# Wheel.net
KiCad netlist of a schematic drawn in EAGLE
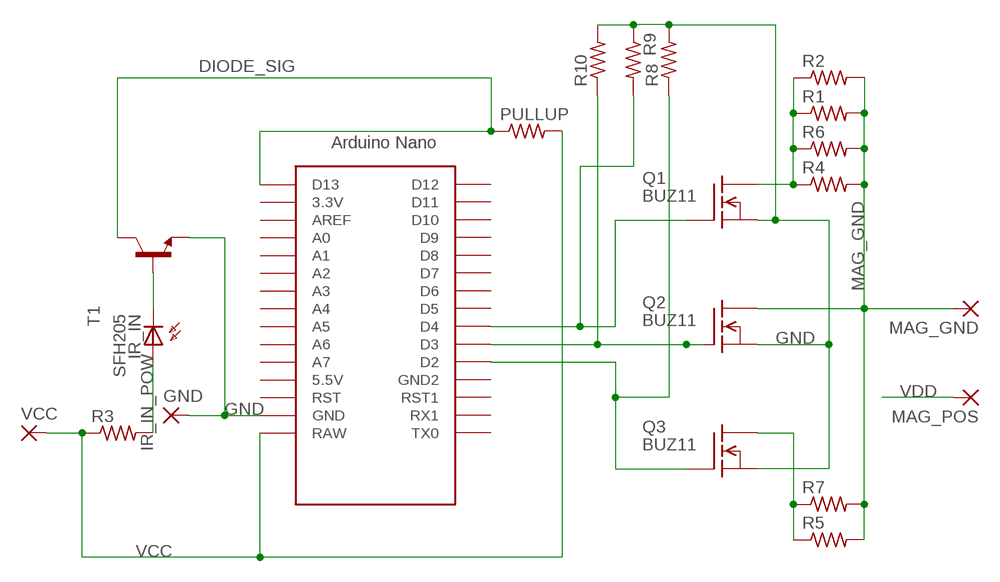
[diagram p0: schematic, sheet 1]

(export (version "E")
  (design (tool "Eeschema 10.0.6"))
  (components
    (comp (ref "GND")
      (value "3,81/1,4")
      (footprint "eagle-import:3,81_1,4")
      (libsource (lib "eagle-import") (part "3,81/1,4"))
    )
    (comp (ref "IR_IN")
      (value "SFH205")
      (footprint "eagle-import:SFH205")
      (libsource (lib "eagle-import") (part "SFH205"))
    )
    (comp (ref "MAG_GND")
      (value "3,81/1,4")
      (footprint "eagle-import:3,81_1,4")
      (libsource (lib "eagle-import") (part "3,81/1,4"))
    )
    (comp (ref "MAG_POS")
      (value "3,81/1,4")
      (footprint "eagle-import:3,81_1,4")
      (libsource (lib "eagle-import") (part "3,81/1,4"))
    )
    (comp (ref "PULLUP")
      (value "R-US_0204/7")
      (footprint "eagle-import:0204_7")
      (libsource (lib "eagle-import") (part "R-US_0204/7"))
    )
    (comp (ref "Q1")
      (value "BUZ11")
      (footprint "eagle-import:TO220")
      (libsource (lib "eagle-import") (part "BUZ11"))
    )
    (comp (ref "Q2")
      (value "BUZ11")
      (footprint "eagle-import:TO220")
      (libsource (lib "eagle-import") (part "BUZ11"))
    )
    (comp (ref "Q3")
      (value "BUZ11")
      (footprint "eagle-import:TO220")
      (libsource (lib "eagle-import") (part "BUZ11"))
    )
    (comp (ref "R1")
      (value "R-US_0204/7")
      (footprint "eagle-import:0204_7")
      (libsource (lib "eagle-import") (part "R-US_0204/7"))
    )
    (comp (ref "R2")
      (value "R-US_0204/7")
      (footprint "eagle-import:0204_7")
      (libsource (lib "eagle-import") (part "R-US_0204/7"))
    )
    (comp (ref "R3")
      (value "R-US_0204/7")
      (footprint "eagle-import:0204_7")
      (libsource (lib "eagle-import") (part "R-US_0204/7"))
    )
    (comp (ref "R4")
      (value "R-US_0204/7")
      (footprint "eagle-import:0204_7")
      (libsource (lib "eagle-import") (part "R-US_0204/7"))
    )
    (comp (ref "R5")
      (value "R-US_0204/7")
      (footprint "eagle-import:0204_7")
      (libsource (lib "eagle-import") (part "R-US_0204/7"))
    )
    (comp (ref "R6")
      (value "R-US_0204/7")
      (footprint "eagle-import:0204_7")
      (libsource (lib "eagle-import") (part "R-US_0204/7"))
    )
    (comp (ref "R7")
      (value "R-US_0204/7")
      (footprint "eagle-import:0204_7")
      (libsource (lib "eagle-import") (part "R-US_0204/7"))
    )
    (comp (ref "R8")
      (value "R-US_0204/7")
      (footprint "eagle-import:0204_7")
      (libsource (lib "eagle-import") (part "R-US_0204/7"))
    )
    (comp (ref "R9")
      (value "R-US_0204/7")
      (footprint "eagle-import:0204_7")
      (libsource (lib "eagle-import") (part "R-US_0204/7"))
    )
    (comp (ref "R10")
      (value "R-US_0204/7")
      (footprint "eagle-import:0204_7")
      (libsource (lib "eagle-import") (part "R-US_0204/7"))
    )
    (comp (ref "T1")
      (value "-NPN-TO92-EBC")
      (footprint "eagle-import:TO92-EBC")
      (libsource (lib "eagle-import") (part "-NPN-TO92-EBC"))
    )
    (comp (ref "U$1")
      (value "NANO")
      (footprint "eagle-import:NANO")
      (libsource (lib "eagle-import") (part "NANO"))
    )
    (comp (ref "VCC")
      (value "3,81/1,4")
      (footprint "eagle-import:3,81_1,4")
      (libsource (lib "eagle-import") (part "3,81/1,4"))
    )
  )
  (nets
    (net (code "1") (name "/DIODE_SIG") (class "Default")
      (node (ref "PULLUP") (pin "1") (pinfunction "1_1") (pintype "passive"))
      (node (ref "T1") (pin "C") (pinfunction "C_C") (pintype "passive"))
      (node (ref "U$1") (pin "D13") (pinfunction "D13_D13") (pintype "bidirectional"))
    )
    (net (code "2") (name "/GND") (class "Default")
      (node (ref "GND") (pin "1") (pinfunction "P_1") (pintype "passive"))
      (node (ref "Q1") (pin "3") (pinfunction "S_3") (pintype "passive"))
      (node (ref "Q2") (pin "3") (pinfunction "S_3") (pintype "passive"))
      (node (ref "Q3") (pin "3") (pinfunction "S_3") (pintype "passive"))
      (node (ref "R10") (pin "2") (pinfunction "2_2") (pintype "passive"))
      (node (ref "R8") (pin "2") (pinfunction "2_2") (pintype "passive"))
      (node (ref "R9") (pin "1") (pinfunction "1_1") (pintype "passive"))
      (node (ref "T1") (pin "E") (pinfunction "E_E") (pintype "passive"))
      (node (ref "U$1") (pin "GND") (pinfunction "GND_GND") (pintype "bidirectional"))
    )
    (net (code "3") (name "/IR_IN_POW") (class "Default")
      (node (ref "IR_IN") (pin "A") (pinfunction "A_A") (pintype "passive"))
      (node (ref "R3") (pin "2") (pinfunction "2_2") (pintype "passive"))
    )
    (net (code "4") (name "/MAG_GND") (class "Default")
      (node (ref "MAG_GND") (pin "1") (pinfunction "P_1") (pintype "passive"))
      (node (ref "Q2") (pin "2") (pinfunction "D_2") (pintype "passive"))
      (node (ref "R1") (pin "2") (pinfunction "2_2") (pintype "passive"))
      (node (ref "R2") (pin "2") (pinfunction "2_2") (pintype "passive"))
      (node (ref "R4") (pin "2") (pinfunction "2_2") (pintype "passive"))
      (node (ref "R5") (pin "2") (pinfunction "2_2") (pintype "passive"))
      (node (ref "R6") (pin "2") (pinfunction "2_2") (pintype "passive"))
      (node (ref "R7") (pin "2") (pinfunction "2_2") (pintype "passive"))
    )
    (net (code "5") (name "/VCC") (class "Default")
      (node (ref "PULLUP") (pin "2") (pinfunction "2_2") (pintype "passive"))
      (node (ref "R3") (pin "1") (pinfunction "1_1") (pintype "passive"))
      (node (ref "U$1") (pin "RAW") (pinfunction "RAW_RAW") (pintype "bidirectional"))
      (node (ref "VCC") (pin "1") (pinfunction "P_1") (pintype "passive"))
    )
    (net (code "6") (name "/VDD") (class "Default")
      (node (ref "MAG_POS") (pin "1") (pinfunction "P_1") (pintype "passive"))
    )
    (net (code "7") (name "Net-(IR_IN-C)") (class "Default")
      (node (ref "IR_IN") (pin "K") (pinfunction "C_K") (pintype "passive"))
      (node (ref "T1") (pin "B") (pinfunction "B_B") (pintype "passive"))
    )
    (net (code "8") (name "Net-(Q1-D)") (class "Default")
      (node (ref "Q1") (pin "2") (pinfunction "D_2") (pintype "passive"))
      (node (ref "R1") (pin "1") (pinfunction "1_1") (pintype "passive"))
      (node (ref "R2") (pin "1") (pinfunction "1_1") (pintype "passive"))
      (node (ref "R4") (pin "1") (pinfunction "1_1") (pintype "passive"))
      (node (ref "R6") (pin "1") (pinfunction "1_1") (pintype "passive"))
    )
    (net (code "9") (name "Net-(Q1-G)") (class "Default")
      (node (ref "Q1") (pin "1") (pinfunction "G_1") (pintype "passive"))
      (node (ref "R9") (pin "2") (pinfunction "2_2") (pintype "passive"))
      (node (ref "U$1") (pin "D4") (pinfunction "D4_D4") (pintype "bidirectional"))
    )
    (net (code "10") (name "Net-(Q2-G)") (class "Default")
      (node (ref "Q2") (pin "1") (pinfunction "G_1") (pintype "passive"))
      (node (ref "R10") (pin "1") (pinfunction "1_1") (pintype "passive"))
      (node (ref "U$1") (pin "D3") (pinfunction "D3_D3") (pintype "bidirectional"))
    )
    (net (code "11") (name "Net-(Q3-D)") (class "Default")
      (node (ref "Q3") (pin "2") (pinfunction "D_2") (pintype "passive"))
      (node (ref "R5") (pin "1") (pinfunction "1_1") (pintype "passive"))
      (node (ref "R7") (pin "1") (pinfunction "1_1") (pintype "passive"))
    )
    (net (code "12") (name "Net-(Q3-G)") (class "Default")
      (node (ref "Q3") (pin "1") (pinfunction "G_1") (pintype "passive"))
      (node (ref "R8") (pin "1") (pinfunction "1_1") (pintype "passive"))
      (node (ref "U$1") (pin "D2") (pinfunction "D2_D2") (pintype "bidirectional"))
    )
    (net (code "13") (name "unconnected-(U$1-5.5V-Pad5V)") (class "Default")
      (node (ref "U$1") (pin "5V") (pinfunction "5.5V_5V") (pintype "bidirectional"))
    )
    (net (code "14") (name "unconnected-(U$1-GND2-PadGND1)") (class "Default")
      (node (ref "U$1") (pin "GND1") (pinfunction "GND2_GND1") (pintype "bidirectional"))
    )
    (net (code "15") (name "unconnected-(U$1-Pad3.3V)") (class "Default")
      (node (ref "U$1") (pin "3.3V") (pinfunction "3.3V_3.3V") (pintype "bidirectional"))
    )
    (net (code "16") (name "unconnected-(U$1-PadA0)") (class "Default")
      (node (ref "U$1") (pin "A0") (pinfunction "A0_A0") (pintype "bidirectional"))
    )
    (net (code "17") (name "unconnected-(U$1-PadA1)") (class "Default")
      (node (ref "U$1") (pin "A1") (pinfunction "A1_A1") (pintype "bidirectional"))
    )
    (net (code "18") (name "unconnected-(U$1-PadA2)") (class "Default")
      (node (ref "U$1") (pin "A2") (pinfunction "A2_A2") (pintype "bidirectional"))
    )
    (net (code "19") (name "unconnected-(U$1-PadA3)") (class "Default")
      (node (ref "U$1") (pin "A3") (pinfunction "A3_A3") (pintype "bidirectional"))
    )
    (net (code "20") (name "unconnected-(U$1-PadA4)") (class "Default")
      (node (ref "U$1") (pin "A4") (pinfunction "A4_A4") (pintype "bidirectional"))
    )
    (net (code "21") (name "unconnected-(U$1-PadA5)") (class "Default")
      (node (ref "U$1") (pin "A5") (pinfunction "A5_A5") (pintype "bidirectional"))
    )
    (net (code "22") (name "unconnected-(U$1-PadA6)") (class "Default")
      (node (ref "U$1") (pin "A6") (pinfunction "A6_A6") (pintype "bidirectional"))
    )
    (net (code "23") (name "unconnected-(U$1-PadA7)") (class "Default")
      (node (ref "U$1") (pin "A7") (pinfunction "A7_A7") (pintype "bidirectional"))
    )
    (net (code "24") (name "unconnected-(U$1-PadAREF)") (class "Default")
      (node (ref "U$1") (pin "AREF") (pinfunction "AREF_AREF") (pintype "bidirectional"))
    )
    (net (code "25") (name "unconnected-(U$1-PadD5)") (class "Default")
      (node (ref "U$1") (pin "D5") (pinfunction "D5_D5") (pintype "bidirectional"))
    )
    (net (code "26") (name "unconnected-(U$1-PadD6)") (class "Default")
      (node (ref "U$1") (pin "D6") (pinfunction "D6_D6") (pintype "bidirectional"))
    )
    (net (code "27") (name "unconnected-(U$1-PadD7)") (class "Default")
      (node (ref "U$1") (pin "D7") (pinfunction "D7_D7") (pintype "bidirectional"))
    )
    (net (code "28") (name "unconnected-(U$1-PadD8)") (class "Default")
      (node (ref "U$1") (pin "D8") (pinfunction "D8_D8") (pintype "bidirectional"))
    )
    (net (code "29") (name "unconnected-(U$1-PadD9)") (class "Default")
      (node (ref "U$1") (pin "D9") (pinfunction "D9_D9") (pintype "bidirectional"))
    )
    (net (code "30") (name "unconnected-(U$1-PadD10)") (class "Default")
      (node (ref "U$1") (pin "D10") (pinfunction "D10_D10") (pintype "bidirectional"))
    )
    (net (code "31") (name "unconnected-(U$1-PadD11)") (class "Default")
      (node (ref "U$1") (pin "D11") (pinfunction "D11_D11") (pintype "bidirectional"))
    )
    (net (code "32") (name "unconnected-(U$1-PadD12)") (class "Default")
      (node (ref "U$1") (pin "D12") (pinfunction "D12_D12") (pintype "bidirectional"))
    )
    (net (code "33") (name "unconnected-(U$1-PadICSP1)") (class "Default")
      (node (ref "U$1") (pin "ICSP1") (pinfunction "ICSP1_ICSP1") (pintype "bidirectional"))
    )
    (net (code "34") (name "unconnected-(U$1-PadICSP2)") (class "Default")
      (node (ref "U$1") (pin "ICSP2") (pinfunction "ICSP2_ICSP2") (pintype "bidirectional"))
    )
    (net (code "35") (name "unconnected-(U$1-PadICSP3)") (class "Default")
      (node (ref "U$1") (pin "ICSP3") (pinfunction "ICSP3_ICSP3") (pintype "bidirectional"))
    )
    (net (code "36") (name "unconnected-(U$1-PadICSP4)") (class "Default")
      (node (ref "U$1") (pin "ICSP4") (pinfunction "ICSP4_ICSP4") (pintype "bidirectional"))
    )
    (net (code "37") (name "unconnected-(U$1-PadICSP5)") (class "Default")
      (node (ref "U$1") (pin "ICSP5") (pinfunction "ICSP5_ICSP5") (pintype "bidirectional"))
    )
    (net (code "38") (name "unconnected-(U$1-PadICSP6)") (class "Default")
      (node (ref "U$1") (pin "ICSP6") (pinfunction "ICSP6_ICSP6") (pintype "bidirectional"))
    )
    (net (code "39") (name "unconnected-(U$1-PadRST)") (class "Default")
      (node (ref "U$1") (pin "RST") (pinfunction "RST_RST") (pintype "bidirectional"))
    )
    (net (code "40") (name "unconnected-(U$1-PadRST1)") (class "Default")
      (node (ref "U$1") (pin "RST1") (pinfunction "RST1_RST1") (pintype "bidirectional"))
    )
    (net (code "41") (name "unconnected-(U$1-PadRX1)") (class "Default")
      (node (ref "U$1") (pin "RX1") (pinfunction "RX1_RX1") (pintype "bidirectional"))
    )
    (net (code "42") (name "unconnected-(U$1-PadTX0)") (class "Default")
      (node (ref "U$1") (pin "TX0") (pinfunction "TX0_TX0") (pintype "bidirectional"))
    )
  )
)
